# Chips.net
KiCad netlist of a schematic drawn in Altium Designer
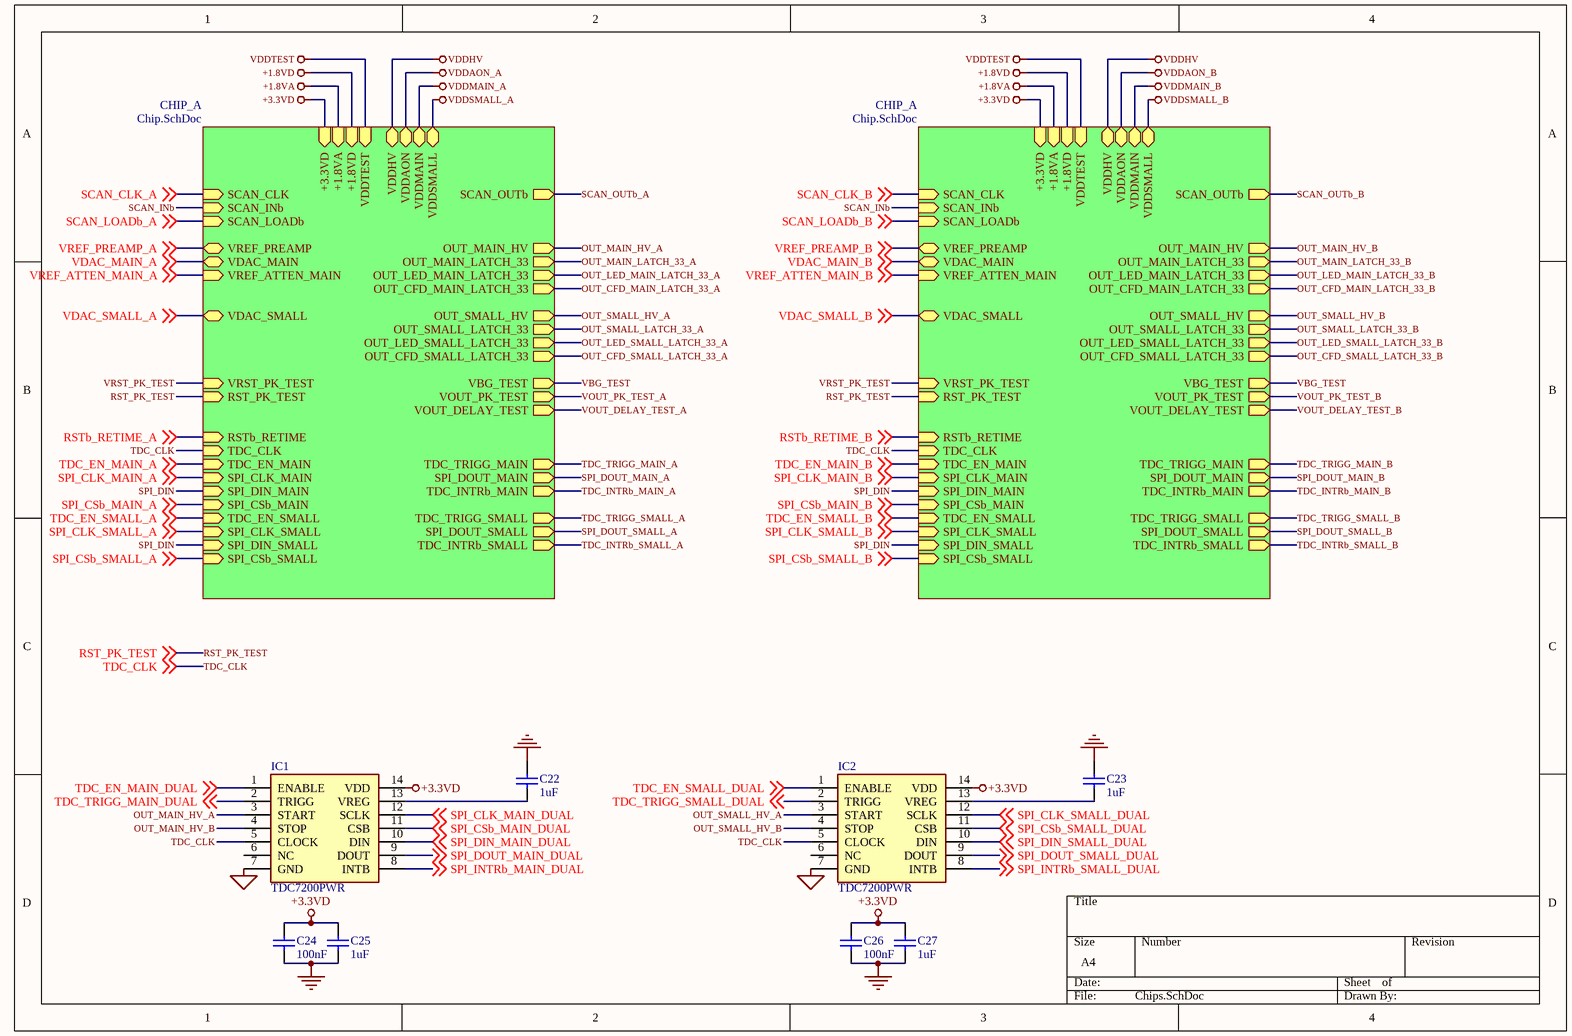
[diagram p0: Chips.SchDoc]

(export (version "E")
  (design (tool "Eeschema 10.0.6"))
  (components
    (comp (ref "C22")
      (value "1uF")
      (footprint "CAPC1608X90X35ML10T15")
      (description "0603")
      (fields (field (name "MANUFACTURER") "Murata"))
      (libsource (lib "Altium Content Vault") (part "CAP-NP-2"))
    )
    (comp (ref "C23")
      (value "1uF")
      (footprint "CAPC1608X90X35ML10T15")
      (description "0603")
      (fields (field (name "MANUFACTURER") "Murata"))
      (libsource (lib "Altium Content Vault") (part "CAP-NP-2"))
    )
    (comp (ref "C24")
      (value "100nF")
      (footprint "CAPC1608X90X35ML10T15")
      (description "0603")
      (fields (field (name "MANUFACTURER") "Murata"))
      (libsource (lib "Altium Content Vault") (part "CAP-NP-2"))
    )
    (comp (ref "C25")
      (value "1uF")
      (footprint "CAPC1608X90X35ML10T15")
      (description "0603")
      (fields (field (name "MANUFACTURER") "Murata"))
      (libsource (lib "Altium Content Vault") (part "CAP-NP-2"))
    )
    (comp (ref "C26")
      (value "100nF")
      (footprint "CAPC1608X90X35ML10T15")
      (description "0603")
      (fields (field (name "MANUFACTURER") "Murata"))
      (libsource (lib "Altium Content Vault") (part "CAP-NP-2"))
    )
    (comp (ref "C27")
      (value "1uF")
      (footprint "CAPC1608X90X35ML10T15")
      (description "0603")
      (fields (field (name "MANUFACTURER") "Murata"))
      (libsource (lib "Altium Content Vault") (part "CAP-NP-2"))
    )
    (comp (ref "IC1")
      (value "TDC7200PWR")
      (footprint "SamacSys:SOP65P640X120-14N")
      (description "Integrated Circuit")
      (libsource (lib "*") (part "TDC7200PWR"))
    )
    (comp (ref "IC2")
      (value "TDC7200PWR")
      (footprint "SamacSys:SOP65P640X120-14N")
      (description "Integrated Circuit")
      (libsource (lib "*") (part "TDC7200PWR"))
    )
  )
  (nets
    (net (code "3") (name "+3.3VD") (class "Default")
      (node (ref "C24") (pin "1") (pinfunction "1_1") (pintype "passive"))
      (node (ref "C25") (pin "1") (pinfunction "1_1") (pintype "passive"))
      (node (ref "C26") (pin "1") (pinfunction "1_1") (pintype "passive"))
      (node (ref "C27") (pin "1") (pinfunction "1_1") (pintype "passive"))
      (node (ref "IC1") (pin "14") (pinfunction "VDD_14") (pintype "passive"))
      (node (ref "IC2") (pin "14") (pinfunction "VDD_14") (pintype "passive"))
    )
    (net (code "12") (name "/OUT_MAIN_HV_A") (class "Default")
      (node (ref "IC1") (pin "3") (pinfunction "START_3") (pintype "passive"))
    )
    (net (code "13") (name "/OUT_MAIN_HV_B") (class "Default")
      (node (ref "IC1") (pin "4") (pinfunction "STOP_4") (pintype "passive"))
    )
    (net (code "16") (name "/OUT_SMALL_HV_A") (class "Default")
      (node (ref "IC2") (pin "3") (pinfunction "START_3") (pintype "passive"))
    )
    (net (code "17") (name "/OUT_SMALL_HV_B") (class "Default")
      (node (ref "IC2") (pin "4") (pinfunction "STOP_4") (pintype "passive"))
    )
    (net (code "42") (name "GND") (class "Default")
      (node (ref "C22") (pin "2") (pinfunction "2_2") (pintype "passive"))
      (node (ref "C23") (pin "2") (pinfunction "2_2") (pintype "passive"))
      (node (ref "C24") (pin "2") (pinfunction "2_2") (pintype "passive"))
      (node (ref "C25") (pin "2") (pinfunction "2_2") (pintype "passive"))
      (node (ref "C26") (pin "2") (pinfunction "2_2") (pintype "passive"))
      (node (ref "C27") (pin "2") (pinfunction "2_2") (pintype "passive"))
      (node (ref "IC1") (pin "7") (pinfunction "GND_7") (pintype "passive"))
      (node (ref "IC2") (pin "7") (pinfunction "GND_7") (pintype "passive"))
    )
    (net (code "43") (name "Net-(IC1-VREG)") (class "Default")
      (node (ref "C22") (pin "1") (pinfunction "1_1") (pintype "passive"))
      (node (ref "IC1") (pin "13") (pinfunction "VREG_13") (pintype "passive"))
    )
    (net (code "44") (name "Net-(IC2-VREG)") (class "Default")
      (node (ref "C23") (pin "1") (pinfunction "1_1") (pintype "passive"))
      (node (ref "IC2") (pin "13") (pinfunction "VREG_13") (pintype "passive"))
    )
    (net (code "54") (name "SPI_CLK_MAIN_DUAL") (class "Default")
      (node (ref "IC1") (pin "12") (pinfunction "SCLK_12") (pintype "passive"))
    )
    (net (code "57") (name "SPI_CLK_SMALL_DUAL") (class "Default")
      (node (ref "IC2") (pin "12") (pinfunction "SCLK_12") (pintype "passive"))
    )
    (net (code "60") (name "SPI_CSb_MAIN_DUAL") (class "Default")
      (node (ref "IC1") (pin "11") (pinfunction "CSB_11") (pintype "passive"))
    )
    (net (code "63") (name "SPI_CSb_SMALL_DUAL") (class "Default")
      (node (ref "IC2") (pin "11") (pinfunction "CSB_11") (pintype "passive"))
    )
    (net (code "64") (name "SPI_DIN_MAIN_DUAL") (class "Default")
      (node (ref "IC1") (pin "10") (pinfunction "DIN_10") (pintype "passive"))
    )
    (net (code "65") (name "SPI_DIN_SMALL_DUAL") (class "Default")
      (node (ref "IC2") (pin "10") (pinfunction "DIN_10") (pintype "passive"))
    )
    (net (code "66") (name "SPI_DOUT_MAIN_DUAL") (class "Default")
      (node (ref "IC1") (pin "9") (pinfunction "DOUT_9") (pintype "passive"))
    )
    (net (code "67") (name "SPI_DOUT_SMALL_DUAL") (class "Default")
      (node (ref "IC2") (pin "9") (pinfunction "DOUT_9") (pintype "passive"))
    )
    (net (code "68") (name "SPI_INTRb_MAIN_DUAL") (class "Default")
      (node (ref "IC1") (pin "8") (pinfunction "INTB_8") (pintype "passive"))
    )
    (net (code "69") (name "SPI_INTRb_SMALL_DUAL") (class "Default")
      (node (ref "IC2") (pin "8") (pinfunction "INTB_8") (pintype "passive"))
    )
    (net (code "70") (name "TDC_CLK") (class "Default")
      (node (ref "IC1") (pin "5") (pinfunction "CLOCK_5") (pintype "passive"))
      (node (ref "IC2") (pin "5") (pinfunction "CLOCK_5") (pintype "passive"))
    )
    (net (code "73") (name "TDC_EN_MAIN_DUAL") (class "Default")
      (node (ref "IC1") (pin "1") (pinfunction "ENABLE_1") (pintype "passive"))
    )
    (net (code "76") (name "TDC_EN_SMALL_DUAL") (class "Default")
      (node (ref "IC2") (pin "1") (pinfunction "ENABLE_1") (pintype "passive"))
    )
    (net (code "77") (name "TDC_TRIGG_MAIN_DUAL") (class "Default")
      (node (ref "IC1") (pin "2") (pinfunction "TRIGG_2") (pintype "passive"))
    )
    (net (code "78") (name "TDC_TRIGG_SMALL_DUAL") (class "Default")
      (node (ref "IC2") (pin "2") (pinfunction "TRIGG_2") (pintype "passive"))
    )
    (net (code "95") (name "unconnected-(IC1-NC-Pad6)") (class "Default")
      (node (ref "IC1") (pin "6") (pinfunction "NC_6") (pintype "passive"))
    )
    (net (code "96") (name "unconnected-(IC2-NC-Pad6)") (class "Default")
      (node (ref "IC2") (pin "6") (pinfunction "NC_6") (pintype "passive"))
    )
  )
)
